# Candle.net
KiCad netlist of a schematic drawn in EAGLE
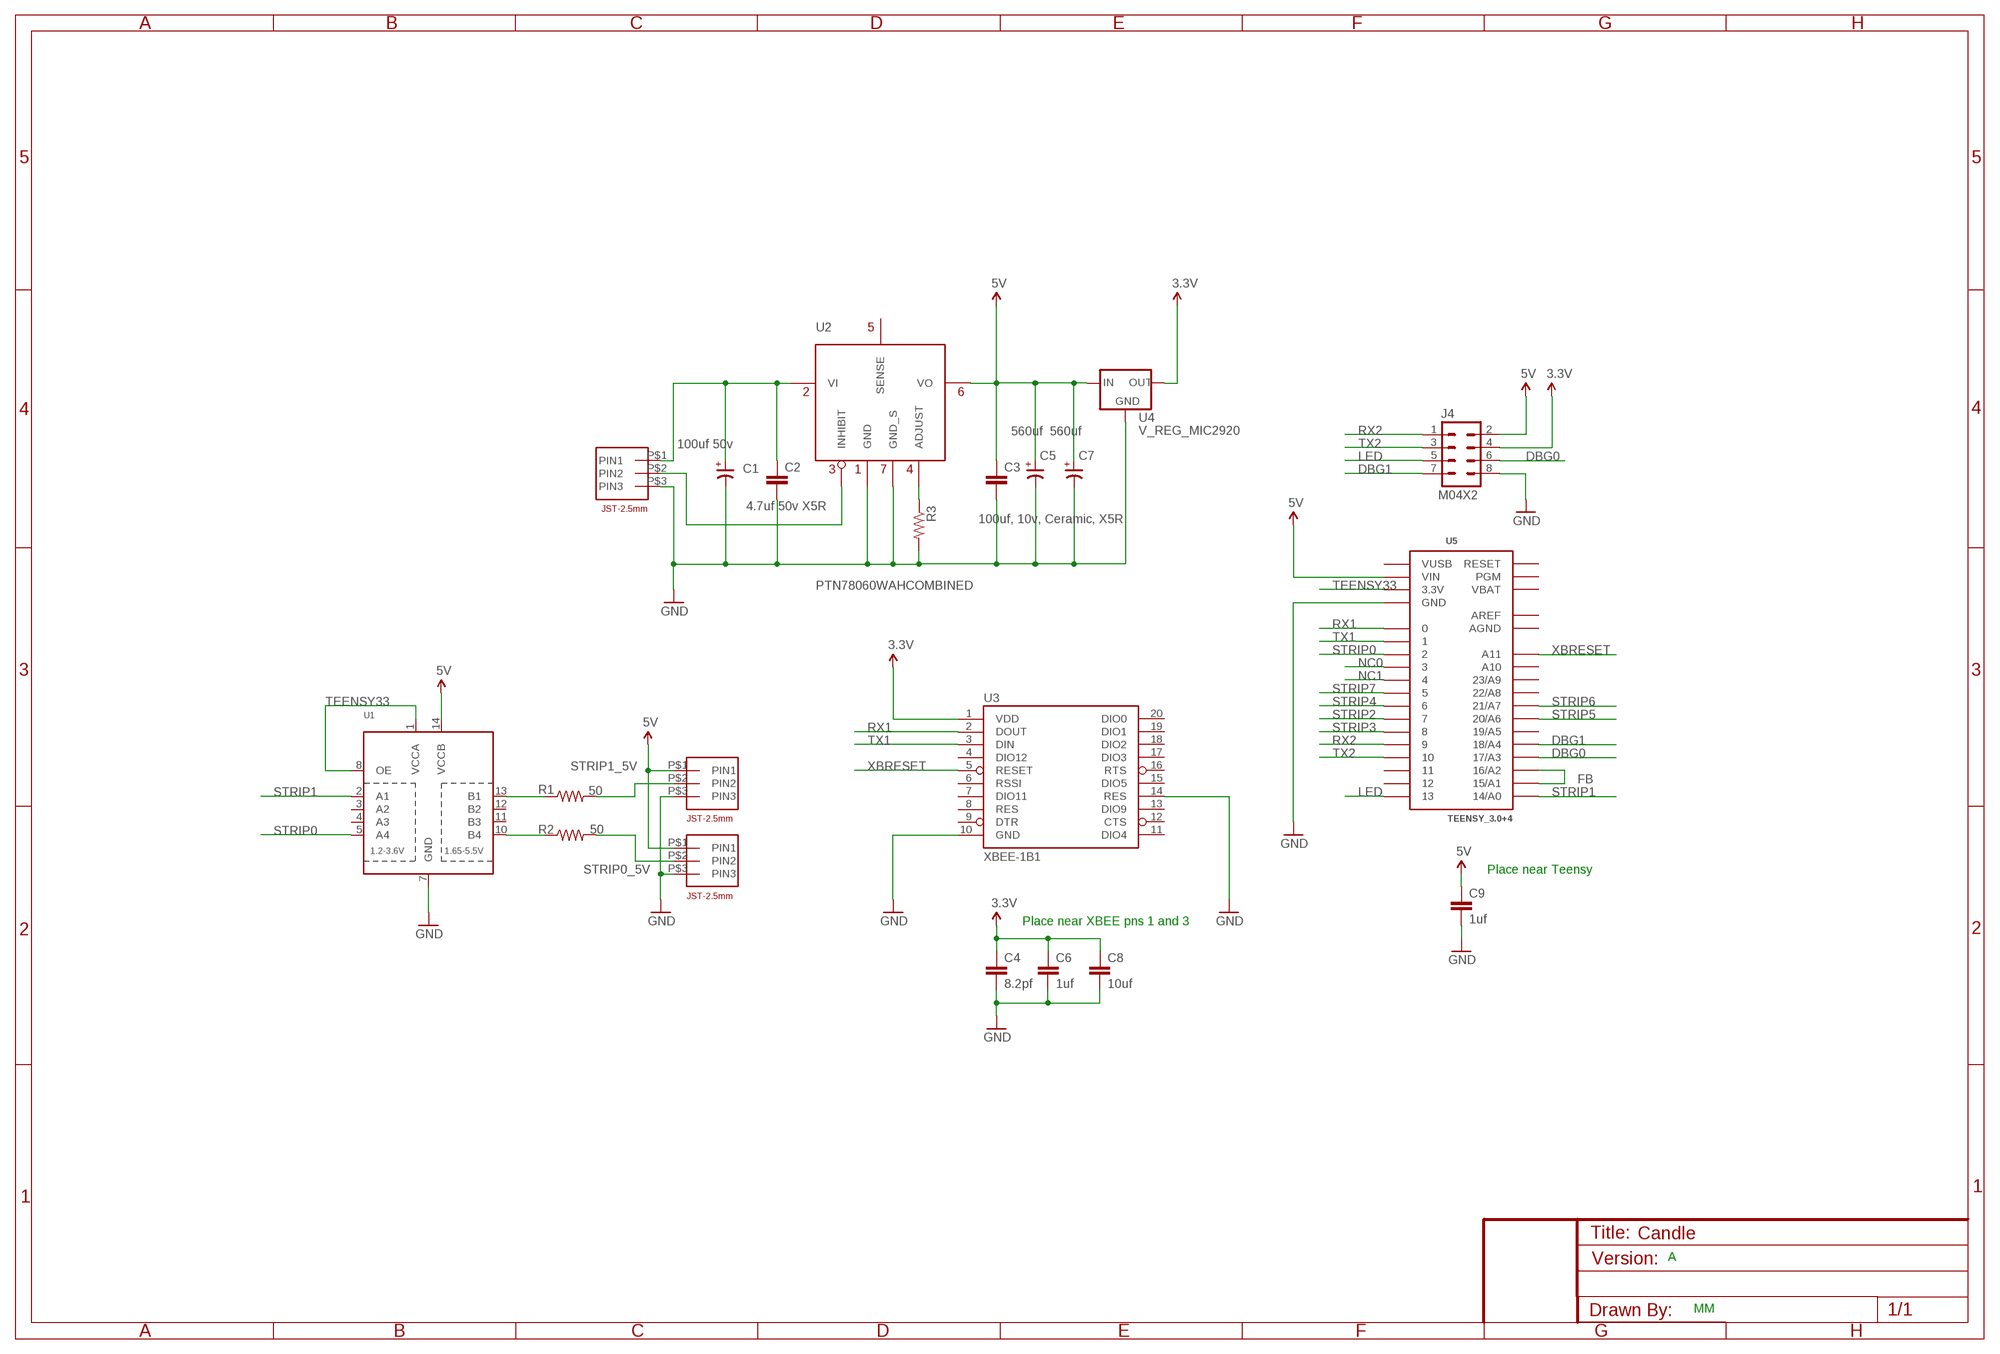
[diagram p0: schematic, sheet 1]

(export (version "E")
  (design (tool "Eeschema 10.0.6"))
  (components
    (comp (ref "C1")
      (value "100uf 50v")
      (footprint "eagle-import:SV-G")
      (libsource (lib "eagle-import") (part "CP-SV-G"))
    )
    (comp (ref "C2")
      (value "4.7uf 50v X5R")
      (footprint "eagle-import:C3225")
      (libsource (lib "eagle-import") (part "C-EUC3225"))
    )
    (comp (ref "C3")
      (value "100uf, 10v, Ceramic, X5R")
      (footprint "eagle-import:C3225")
      (libsource (lib "eagle-import") (part "C-EUC3225"))
    )
    (comp (ref "C4")
      (value "8.2pf")
      (footprint "eagle-import:C3225")
      (libsource (lib "eagle-import") (part "C-EUC3225"))
    )
    (comp (ref "C5")
      (value "560uf")
      (footprint "eagle-import:SV-G")
      (libsource (lib "eagle-import") (part "CP-SV-G"))
    )
    (comp (ref "C6")
      (value "1uf")
      (footprint "eagle-import:C3225")
      (libsource (lib "eagle-import") (part "C-EUC3225"))
    )
    (comp (ref "C7")
      (value "560uf")
      (footprint "eagle-import:SV-G")
      (libsource (lib "eagle-import") (part "CP-SV-G"))
    )
    (comp (ref "C8")
      (value "10uf")
      (footprint "eagle-import:C3225")
      (libsource (lib "eagle-import") (part "C-EUC3225"))
    )
    (comp (ref "C9")
      (value "1uf")
      (footprint "eagle-import:C3225")
      (libsource (lib "eagle-import") (part "C-EUC3225"))
    )
    (comp (ref "J1")
      (value "JST-XH-2.5MM-SIDE-3")
      (footprint "eagle-import:JST-XH-2.5MM-SIDE-3")
      (libsource (lib "eagle-import") (part "JST-XH-2.5MM-SIDE-3"))
    )
    (comp (ref "J2")
      (value "JST-XH-2.5MM-SIDE-3")
      (footprint "eagle-import:JST-XH-2.5MM-SIDE-3")
      (libsource (lib "eagle-import") (part "JST-XH-2.5MM-SIDE-3"))
    )
    (comp (ref "J3")
      (value "JST-XH-2.5MM-SIDE-3")
      (footprint "eagle-import:JST-XH-2.5MM-SIDE-3")
      (libsource (lib "eagle-import") (part "JST-XH-2.5MM-SIDE-3"))
    )
    (comp (ref "J4")
      (value "M04X2")
      (footprint "eagle-import:2X4")
      (libsource (lib "eagle-import") (part "M04X2"))
    )
    (comp (ref "R1")
      (value "50")
      (footprint "eagle-import:R0805")
      (libsource (lib "eagle-import") (part "R-US_R0805"))
    )
    (comp (ref "R2")
      (value "50")
      (footprint "eagle-import:R0805")
      (libsource (lib "eagle-import") (part "R-US_R0805"))
    )
    (comp (ref "R3")
      (value "R-US_R0805")
      (footprint "eagle-import:R0805")
      (libsource (lib "eagle-import") (part "R-US_R0805"))
    )
    (comp (ref "U1")
      (value "TXB0104PWRSOIC14")
      (footprint "eagle-import:SO14")
      (libsource (lib "eagle-import") (part "TXB0104PWRSOIC14"))
    )
    (comp (ref "U2")
      (value "PTN78060WAHCOMBINED")
      (footprint "eagle-import:COMBINED")
      (libsource (lib "eagle-import") (part "PTN78060WAHCOMBINED"))
    )
    (comp (ref "U3")
      (value "XBEE-1B1")
      (footprint "eagle-import:XBEE-1")
      (libsource (lib "eagle-import") (part "XBEE-1B1"))
    )
    (comp (ref "U4")
      (value "V_REG_MIC2920")
      (footprint "eagle-import:SOT223")
      (libsource (lib "eagle-import") (part "V_REG_MIC2920"))
    )
    (comp (ref "U5")
      (value "TEENSY_3.0+4")
      (footprint "eagle-import:TEENSY_3.0+4")
      (libsource (lib "eagle-import") (part "TEENSY_3.0+4"))
    )
  )
  (nets
    (net (code "1") (name "/AGND") (class "Default")
      (node (ref "U5") (pin "AGND") (pinfunction "AGND_AGND") (pintype "power_in"))
    )
    (net (code "2") (name "/AREF") (class "Default")
      (node (ref "U5") (pin "AREF") (pinfunction "AREF_AREF") (pintype "power_in"))
    )
    (net (code "3") (name "/DBG0") (class "Default")
      (node (ref "J4") (pin "6") (pinfunction "6_6") (pintype "passive"))
      (node (ref "U5") (pin "17/A3") (pinfunction "17/A3_17/A3") (pintype "bidirectional"))
    )
    (net (code "4") (name "/DBG1") (class "Default")
      (node (ref "J4") (pin "7") (pinfunction "7_7") (pintype "passive"))
      (node (ref "U5") (pin "18/A4") (pinfunction "18/A4_18/A4") (pintype "bidirectional"))
    )
    (net (code "5") (name "/FB") (class "Default")
      (node (ref "U5") (pin "15/A1") (pinfunction "15/A1_15/A1") (pintype "bidirectional"))
      (node (ref "U5") (pin "16/A2") (pinfunction "16/A2_16/A2") (pintype "bidirectional"))
    )
    (net (code "6") (name "/LED") (class "Default")
      (node (ref "J4") (pin "5") (pinfunction "5_5") (pintype "passive"))
      (node (ref "U5") (pin "13") (pinfunction "13_13") (pintype "bidirectional"))
    )
    (net (code "7") (name "/NC0") (class "Default")
      (node (ref "U5") (pin "3") (pinfunction "3_3") (pintype "bidirectional"))
    )
    (net (code "8") (name "/NC1") (class "Default")
      (node (ref "U5") (pin "4") (pinfunction "4_4") (pintype "bidirectional"))
    )
    (net (code "9") (name "/RX1") (class "Default")
      (node (ref "U3") (pin "2") (pinfunction "DOUT_2") (pintype "output"))
      (node (ref "U5") (pin "0") (pinfunction "0_0") (pintype "bidirectional"))
    )
    (net (code "10") (name "/RX2") (class "Default")
      (node (ref "J4") (pin "1") (pinfunction "1_1") (pintype "passive"))
      (node (ref "U5") (pin "9") (pinfunction "9_9") (pintype "bidirectional"))
    )
    (net (code "11") (name "/STRIP0") (class "Default")
      (node (ref "U1") (pin "5") (pinfunction "A4_5") (pintype "bidirectional"))
      (node (ref "U5") (pin "2") (pinfunction "2_2") (pintype "bidirectional"))
    )
    (net (code "12") (name "/STRIP0_5V") (class "Default")
      (node (ref "J3") (pin "P$2") (pinfunction "PIN2_P$2") (pintype "bidirectional"))
      (node (ref "R2") (pin "2") (pinfunction "2_2") (pintype "passive"))
    )
    (net (code "13") (name "/STRIP1") (class "Default")
      (node (ref "U1") (pin "2") (pinfunction "A1_2") (pintype "bidirectional"))
      (node (ref "U5") (pin "14/A0") (pinfunction "14/A0_14/A0") (pintype "bidirectional"))
    )
    (net (code "14") (name "/STRIP1_5V") (class "Default")
      (node (ref "J2") (pin "P$2") (pinfunction "PIN2_P$2") (pintype "bidirectional"))
      (node (ref "R1") (pin "2") (pinfunction "2_2") (pintype "passive"))
    )
    (net (code "15") (name "/STRIP2") (class "Default")
      (node (ref "U5") (pin "7") (pinfunction "7_7") (pintype "bidirectional"))
    )
    (net (code "16") (name "/STRIP3") (class "Default")
      (node (ref "U5") (pin "8") (pinfunction "8_8") (pintype "bidirectional"))
    )
    (net (code "17") (name "/STRIP4") (class "Default")
      (node (ref "U5") (pin "6") (pinfunction "6_6") (pintype "bidirectional"))
    )
    (net (code "18") (name "/STRIP5") (class "Default")
      (node (ref "U5") (pin "20/A6") (pinfunction "20/A6_20/A6") (pintype "bidirectional"))
    )
    (net (code "19") (name "/STRIP6") (class "Default")
      (node (ref "U5") (pin "21/A7") (pinfunction "21/A7_21/A7") (pintype "bidirectional"))
    )
    (net (code "20") (name "/STRIP7") (class "Default")
      (node (ref "U5") (pin "5") (pinfunction "5_5") (pintype "bidirectional"))
    )
    (net (code "21") (name "/TEENSY33") (class "Default")
      (node (ref "U1") (pin "1") (pinfunction "VCCA_1") (pintype "bidirectional"))
      (node (ref "U1") (pin "8") (pinfunction "OE_8") (pintype "bidirectional"))
      (node (ref "U5") (pin "3.3V") (pinfunction "3.3V_3.3V") (pintype "power_in"))
      (node (ref "U5") (pin "3.3V1") (pinfunction "3.3V_3.3V1") (pintype "power_in"))
    )
    (net (code "22") (name "/TX1") (class "Default")
      (node (ref "U3") (pin "3") (pinfunction "DIN_3") (pintype "input"))
      (node (ref "U5") (pin "1") (pinfunction "1_1") (pintype "bidirectional"))
    )
    (net (code "23") (name "/TX2") (class "Default")
      (node (ref "J4") (pin "3") (pinfunction "3_3") (pintype "passive"))
      (node (ref "U5") (pin "10") (pinfunction "10_10") (pintype "bidirectional"))
    )
    (net (code "24") (name "/VBAT") (class "Default")
      (node (ref "U5") (pin "VBAT") (pinfunction "VBAT_VBAT") (pintype "power_in"))
    )
    (net (code "25") (name "/VUSB") (class "Default")
      (node (ref "U5") (pin "VUSB") (pinfunction "VUSB_VUSB") (pintype "power_in"))
    )
    (net (code "26") (name "/XBRESET") (class "Default")
      (node (ref "U3") (pin "5") (pinfunction "RESET_5") (pintype "input"))
      (node (ref "U5") (pin "A11") (pinfunction "A11_A11") (pintype "bidirectional"))
    )
    (net (code "27") (name "3.3V") (class "Default")
      (node (ref "C4") (pin "1") (pinfunction "1_1") (pintype "passive"))
      (node (ref "C6") (pin "1") (pinfunction "1_1") (pintype "passive"))
      (node (ref "C8") (pin "1") (pinfunction "1_1") (pintype "passive"))
      (node (ref "J4") (pin "4") (pinfunction "4_4") (pintype "passive"))
      (node (ref "U3") (pin "1") (pinfunction "VDD_1") (pintype "power_in"))
      (node (ref "U4") (pin "3") (pinfunction "OUT_3") (pintype "output"))
    )
    (net (code "28") (name "5V") (class "Default")
      (node (ref "C3") (pin "1") (pinfunction "1_1") (pintype "passive"))
      (node (ref "C5") (pin "+") (pinfunction "+_+") (pintype "passive"))
      (node (ref "C7") (pin "+") (pinfunction "+_+") (pintype "passive"))
      (node (ref "C9") (pin "1") (pinfunction "1_1") (pintype "passive"))
      (node (ref "J2") (pin "P$1") (pinfunction "PIN1_P$1") (pintype "bidirectional"))
      (node (ref "J3") (pin "P$1") (pinfunction "PIN1_P$1") (pintype "bidirectional"))
      (node (ref "J4") (pin "2") (pinfunction "2_2") (pintype "passive"))
      (node (ref "U1") (pin "14") (pinfunction "VCCB_14") (pintype "bidirectional"))
      (node (ref "U2") (pin "VOUT") (pinfunction "VO_VOUT") (pintype "bidirectional"))
      (node (ref "U2") (pin "VOUT_S") (pinfunction "VO_VOUT_S") (pintype "bidirectional"))
      (node (ref "U4") (pin "1") (pinfunction "IN_1") (pintype "input"))
      (node (ref "U5") (pin "VIN") (pinfunction "VIN_VIN") (pintype "power_in"))
    )
    (net (code "29") (name "GND") (class "Default")
      (node (ref "C1") (pin "-") (pinfunction "-_-") (pintype "passive"))
      (node (ref "C2") (pin "2") (pinfunction "2_2") (pintype "passive"))
      (node (ref "C3") (pin "2") (pinfunction "2_2") (pintype "passive"))
      (node (ref "C4") (pin "2") (pinfunction "2_2") (pintype "passive"))
      (node (ref "C5") (pin "-") (pinfunction "-_-") (pintype "passive"))
      (node (ref "C6") (pin "2") (pinfunction "2_2") (pintype "passive"))
      (node (ref "C7") (pin "-") (pinfunction "-_-") (pintype "passive"))
      (node (ref "C8") (pin "2") (pinfunction "2_2") (pintype "passive"))
      (node (ref "C9") (pin "2") (pinfunction "2_2") (pintype "passive"))
      (node (ref "J1") (pin "P$3") (pinfunction "PIN3_P$3") (pintype "bidirectional"))
      (node (ref "J2") (pin "P$3") (pinfunction "PIN3_P$3") (pintype "bidirectional"))
      (node (ref "J3") (pin "P$3") (pinfunction "PIN3_P$3") (pintype "bidirectional"))
      (node (ref "J4") (pin "8") (pinfunction "8_8") (pintype "passive"))
      (node (ref "R3") (pin "2") (pinfunction "2_2") (pintype "passive"))
      (node (ref "U1") (pin "7") (pinfunction "GND_7") (pintype "bidirectional"))
      (node (ref "U2") (pin "GND") (pinfunction "GND_GND") (pintype "bidirectional"))
      (node (ref "U2") (pin "GND_S") (pinfunction "GND_GND_S") (pintype "bidirectional"))
      (node (ref "U2") (pin "S/GND") (pinfunction "GND_S_S/GND") (pintype "bidirectional"))
      (node (ref "U2") (pin "S/GND_S") (pinfunction "GND_S_S/GND_S") (pintype "bidirectional"))
      (node (ref "U3") (pin "10") (pinfunction "GND_10") (pintype "power_in"))
      (node (ref "U3") (pin "14") (pinfunction "RES_14") (pintype "bidirectional"))
      (node (ref "U4") (pin "2") (pinfunction "GND_2") (pintype "input"))
      (node (ref "U4") (pin "4") (pinfunction "GND_4") (pintype "input"))
      (node (ref "U5") (pin "GND") (pinfunction "GND_GND") (pintype "power_in"))
      (node (ref "U5") (pin "GND1") (pinfunction "GND_GND1") (pintype "power_in"))
    )
    (net (code "30") (name "Net-(J1-PIN1)") (class "Default")
      (node (ref "C1") (pin "+") (pinfunction "+_+") (pintype "passive"))
      (node (ref "C2") (pin "1") (pinfunction "1_1") (pintype "passive"))
      (node (ref "J1") (pin "P$1") (pinfunction "PIN1_P$1") (pintype "bidirectional"))
      (node (ref "U2") (pin "VIN") (pinfunction "VI_VIN") (pintype "bidirectional"))
      (node (ref "U2") (pin "VIN_S") (pinfunction "VI_VIN_S") (pintype "bidirectional"))
    )
    (net (code "31") (name "Net-(J1-PIN2)") (class "Default")
      (node (ref "J1") (pin "P$2") (pinfunction "PIN2_P$2") (pintype "bidirectional"))
      (node (ref "U2") (pin "EN") (pinfunction "INHIBIT_EN") (pintype "bidirectional"))
    )
    (net (code "32") (name "Net-(R3-Pad1)") (class "Default")
      (node (ref "R3") (pin "1") (pinfunction "1_1") (pintype "passive"))
      (node (ref "U2") (pin "ADJUST") (pinfunction "ADJUST_ADJUST") (pintype "bidirectional"))
    )
    (net (code "33") (name "Net-(U1-B1)") (class "Default")
      (node (ref "R1") (pin "1") (pinfunction "1_1") (pintype "passive"))
      (node (ref "U1") (pin "13") (pinfunction "B1_13") (pintype "bidirectional"))
    )
    (net (code "34") (name "Net-(U1-B4)") (class "Default")
      (node (ref "R2") (pin "1") (pinfunction "1_1") (pintype "passive"))
      (node (ref "U1") (pin "10") (pinfunction "B4_10") (pintype "bidirectional"))
    )
    (net (code "35") (name "unconnected-(U1-A2-Pad3)") (class "Default")
      (node (ref "U1") (pin "3") (pinfunction "A2_3") (pintype "bidirectional"))
    )
    (net (code "36") (name "unconnected-(U1-A3-Pad4)") (class "Default")
      (node (ref "U1") (pin "4") (pinfunction "A3_4") (pintype "bidirectional"))
    )
    (net (code "37") (name "unconnected-(U1-B2-Pad12)") (class "Default")
      (node (ref "U1") (pin "12") (pinfunction "B2_12") (pintype "bidirectional"))
    )
    (net (code "38") (name "unconnected-(U1-B3-Pad11)") (class "Default")
      (node (ref "U1") (pin "11") (pinfunction "B3_11") (pintype "bidirectional"))
    )
    (net (code "39") (name "unconnected-(U2-PadSENSE)") (class "Default")
      (node (ref "U2") (pin "SENSE") (pinfunction "SENSE_SENSE") (pintype "bidirectional"))
    )
    (net (code "40") (name "unconnected-(U3-CTS-Pad12)") (class "Default")
      (node (ref "U3") (pin "12") (pinfunction "CTS_12") (pintype "output"))
    )
    (net (code "41") (name "unconnected-(U3-DIO0-Pad20)") (class "Default")
      (node (ref "U3") (pin "20") (pinfunction "DIO0_20") (pintype "bidirectional"))
    )
    (net (code "42") (name "unconnected-(U3-DIO1-Pad19)") (class "Default")
      (node (ref "U3") (pin "19") (pinfunction "DIO1_19") (pintype "bidirectional"))
    )
    (net (code "43") (name "unconnected-(U3-DIO2-Pad18)") (class "Default")
      (node (ref "U3") (pin "18") (pinfunction "DIO2_18") (pintype "bidirectional"))
    )
    (net (code "44") (name "unconnected-(U3-DIO3-Pad17)") (class "Default")
      (node (ref "U3") (pin "17") (pinfunction "DIO3_17") (pintype "bidirectional"))
    )
    (net (code "45") (name "unconnected-(U3-DIO4-Pad11)") (class "Default")
      (node (ref "U3") (pin "11") (pinfunction "DIO4_11") (pintype "bidirectional"))
    )
    (net (code "46") (name "unconnected-(U3-DIO5-Pad15)") (class "Default")
      (node (ref "U3") (pin "15") (pinfunction "DIO5_15") (pintype "bidirectional"))
    )
    (net (code "47") (name "unconnected-(U3-DIO9-Pad13)") (class "Default")
      (node (ref "U3") (pin "13") (pinfunction "DIO9_13") (pintype "bidirectional"))
    )
    (net (code "48") (name "unconnected-(U3-DIO11-Pad7)") (class "Default")
      (node (ref "U3") (pin "7") (pinfunction "DIO11_7") (pintype "bidirectional"))
    )
    (net (code "49") (name "unconnected-(U3-DIO12-Pad4)") (class "Default")
      (node (ref "U3") (pin "4") (pinfunction "DIO12_4") (pintype "bidirectional"))
    )
    (net (code "50") (name "unconnected-(U3-DTR-Pad9)") (class "Default")
      (node (ref "U3") (pin "9") (pinfunction "DTR_9") (pintype "bidirectional"))
    )
    (net (code "51") (name "unconnected-(U3-RES-Pad8)") (class "Default")
      (node (ref "U3") (pin "8") (pinfunction "RES_8") (pintype "bidirectional"))
    )
    (net (code "52") (name "unconnected-(U3-RSSI-Pad6)") (class "Default")
      (node (ref "U3") (pin "6") (pinfunction "RSSI_6") (pintype "bidirectional"))
    )
    (net (code "53") (name "unconnected-(U3-RTS-Pad16)") (class "Default")
      (node (ref "U3") (pin "16") (pinfunction "RTS_16") (pintype "input"))
    )
    (net (code "54") (name "unconnected-(U5-Pad11)") (class "Default")
      (node (ref "U5") (pin "11") (pinfunction "11_11") (pintype "bidirectional"))
    )
    (net (code "55") (name "unconnected-(U5-Pad12)") (class "Default")
      (node (ref "U5") (pin "12") (pinfunction "12_12") (pintype "bidirectional"))
    )
    (net (code "56") (name "unconnected-(U5-Pad19{slash}A5)") (class "Default")
      (node (ref "U5") (pin "19/A5") (pinfunction "19/A5_19/A5") (pintype "bidirectional"))
    )
    (net (code "57") (name "unconnected-(U5-Pad22{slash}A8)") (class "Default")
      (node (ref "U5") (pin "22/A8") (pinfunction "22/A8_22/A8") (pintype "bidirectional"))
    )
    (net (code "58") (name "unconnected-(U5-Pad23{slash}A9)") (class "Default")
      (node (ref "U5") (pin "23/A9") (pinfunction "23/A9_23/A9") (pintype "bidirectional"))
    )
    (net (code "59") (name "unconnected-(U5-PadA10)") (class "Default")
      (node (ref "U5") (pin "A10") (pinfunction "A10_A10") (pintype "bidirectional"))
    )
    (net (code "60") (name "unconnected-(U5-PadPGM)") (class "Default")
      (node (ref "U5") (pin "PGM") (pinfunction "PGM_PGM") (pintype "bidirectional"))
    )
    (net (code "61") (name "unconnected-(U5-PadRESET)") (class "Default")
      (node (ref "U5") (pin "RESET") (pinfunction "RESET_RESET") (pintype "bidirectional"))
    )
  )
)
